# primary_cap_int_-_Copy.net
KiCad netlist of a schematic drawn in Altium Designer
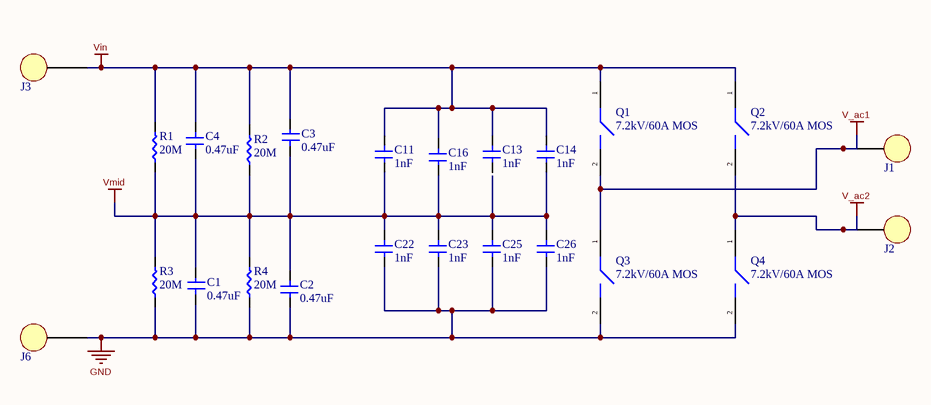
[diagram p0: primary_cap_int - Copy.SchDoc]

(export (version "E")
  (design (tool "Eeschema 10.0.6"))
  (components
    (comp (ref "C1")
      (value "0.47uF")
      (footprint "C4BSYBX3470ZBMJ")
      (description "Cap, 0.47UF, 750VAC, Film, Radial")
      (fields
        (field (name "MANUFACTURER") "KEMET")
        (field (name "MANUFACTURER PART NUMBER") "C4BSYBX3470ZBMJ")
      )
      (libsource (lib "primary_cap") (part "C4BSYBX3470ZBMJ"))
    )
    (comp (ref "C2")
      (value "0.47uF")
      (footprint "C4BSYBX3470ZBMJ")
      (description "Cap, 0.47UF, 750VAC, Film, Radial")
      (fields
        (field (name "MANUFACTURER") "KEMET")
        (field (name "MANUFACTURER PART NUMBER") "C4BSYBX3470ZBMJ")
      )
      (libsource (lib "primary_cap") (part "C4BSYBX3470ZBMJ"))
    )
    (comp (ref "C3")
      (value "0.47uF")
      (footprint "C4BSYBX3470ZBMJ")
      (description "Cap, 0.47UF, 750VAC, Film, Radial")
      (fields
        (field (name "MANUFACTURER") "KEMET")
        (field (name "MANUFACTURER PART NUMBER") "C4BSYBX3470ZBMJ")
      )
      (libsource (lib "primary_cap") (part "C4BSYBX3470ZBMJ"))
    )
    (comp (ref "C4")
      (value "0.47uF")
      (footprint "C4BSYBX3470ZBMJ")
      (description "Cap, 0.47UF, 750VAC, Film, Radial")
      (fields
        (field (name "MANUFACTURER") "KEMET")
        (field (name "MANUFACTURER PART NUMBER") "C4BSYBX3470ZBMJ")
      )
      (libsource (lib "primary_cap") (part "C4BSYBX3470ZBMJ"))
    )
    (comp (ref "C11")
      (value "1nF")
      (footprint "PHE450XB4100JB04R17")
      (description "CAP FILM 1000PF 5% 3KVDC RADIAL")
      (fields
        (field (name "MANUFACTURER") "KEMET")
        (field (name "MANUFACTURER PART NUMBER") "PHE450XB4100JB04R17")
      )
      (libsource (lib "primary_cap") (part "PHE450XB4100JB04R17"))
    )
    (comp (ref "C13")
      (value "1nF")
      (footprint "PHE450XB4100JB04R17")
      (description "CAP FILM 1000PF 5% 3KVDC RADIAL")
      (fields
        (field (name "MANUFACTURER") "KEMET")
        (field (name "MANUFACTURER PART NUMBER") "PHE450XB4100JB04R17")
      )
      (libsource (lib "primary_cap") (part "PHE450XB4100JB04R17"))
    )
    (comp (ref "C14")
      (value "1nF")
      (footprint "PHE450XB4100JB04R17")
      (description "CAP FILM 1000PF 5% 3KVDC RADIAL")
      (fields
        (field (name "MANUFACTURER") "KEMET")
        (field (name "MANUFACTURER PART NUMBER") "PHE450XB4100JB04R17")
      )
      (libsource (lib "primary_cap") (part "PHE450XB4100JB04R17"))
    )
    (comp (ref "C16")
      (value "1nF")
      (footprint "PHE450XB4100JB04R17")
      (description "CAP FILM 1000PF 5% 3KVDC RADIAL")
      (fields
        (field (name "MANUFACTURER") "KEMET")
        (field (name "MANUFACTURER PART NUMBER") "PHE450XB4100JB04R17")
      )
      (libsource (lib "primary_cap") (part "PHE450XB4100JB04R17"))
    )
    (comp (ref "C22")
      (value "1nF")
      (footprint "PHE450XB4100JB04R17")
      (description "CAP FILM 1000PF 5% 3KVDC RADIAL")
      (fields
        (field (name "MANUFACTURER") "KEMET")
        (field (name "MANUFACTURER PART NUMBER") "PHE450XB4100JB04R17")
      )
      (libsource (lib "primary_cap") (part "PHE450XB4100JB04R17"))
    )
    (comp (ref "C23")
      (value "1nF")
      (footprint "PHE450XB4100JB04R17")
      (description "CAP FILM 1000PF 5% 3KVDC RADIAL")
      (fields
        (field (name "MANUFACTURER") "KEMET")
        (field (name "MANUFACTURER PART NUMBER") "PHE450XB4100JB04R17")
      )
      (libsource (lib "primary_cap") (part "PHE450XB4100JB04R17"))
    )
    (comp (ref "C25")
      (value "1nF")
      (footprint "PHE450XB4100JB04R17")
      (description "CAP FILM 1000PF 5% 3KVDC RADIAL")
      (fields
        (field (name "MANUFACTURER") "KEMET")
        (field (name "MANUFACTURER PART NUMBER") "PHE450XB4100JB04R17")
      )
      (libsource (lib "primary_cap") (part "PHE450XB4100JB04R17"))
    )
    (comp (ref "C26")
      (value "1nF")
      (footprint "PHE450XB4100JB04R17")
      (description "CAP FILM 1000PF 5% 3KVDC RADIAL")
      (fields
        (field (name "MANUFACTURER") "KEMET")
        (field (name "MANUFACTURER PART NUMBER") "PHE450XB4100JB04R17")
      )
      (libsource (lib "primary_cap") (part "PHE450XB4100JB04R17"))
    )
    (comp (ref "J1")
      (value "TERM PCB SNAP-IN VERT HD M5 THRD")
      (footprint "M4_9pin_shank")
      (fields
        (field (name "MANUFACTURER") "Keystone Electronics")
        (field (name "MANUFACTURER PART NUMBER") "7807")
      )
      (libsource (lib "diodebridge") (part "7807"))
    )
    (comp (ref "J2")
      (value "TERM PCB SNAP-IN VERT HD M5 THRD")
      (footprint "M4_9pin_shank")
      (fields
        (field (name "MANUFACTURER") "Keystone Electronics")
        (field (name "MANUFACTURER PART NUMBER") "7807")
      )
      (libsource (lib "diodebridge") (part "7807"))
    )
    (comp (ref "J3")
      (value "TERM PCB SNAP-IN VERT HD M5 THRD")
      (footprint "M4_9pin_shank")
      (fields
        (field (name "MANUFACTURER") "Keystone Electronics")
        (field (name "MANUFACTURER PART NUMBER") "7807")
      )
      (libsource (lib "diodebridge") (part "7807"))
    )
    (comp (ref "J6")
      (value "TERM PCB SNAP-IN VERT HD M5 THRD")
      (footprint "M4_9pin_shank")
      (fields
        (field (name "MANUFACTURER") "Keystone Electronics")
        (field (name "MANUFACTURER PART NUMBER") "7807")
      )
      (libsource (lib "diodebridge") (part "7807"))
    )
    (comp (ref "Q1")
      (value "7.2kV/60A MOS")
      (footprint "Austin Supermos_r1")
      (libsource (lib "primary_cap") (part "Austin SuperMos"))
    )
    (comp (ref "Q2")
      (value "7.2kV/60A MOS")
      (footprint "Austin Supermos_r1")
      (libsource (lib "primary_cap") (part "Austin SuperMos"))
    )
    (comp (ref "Q3")
      (value "7.2kV/60A MOS")
      (footprint "Austin Supermos_r1")
      (libsource (lib "primary_cap") (part "Austin SuperMos"))
    )
    (comp (ref "Q4")
      (value "7.2kV/60A MOS")
      (footprint "Austin Supermos_r1")
      (libsource (lib "primary_cap") (part "Austin SuperMos"))
    )
    (comp (ref "R1")
      (value "20M")
      (footprint "VR37000002005JR500")
      (description "RES 20M OHM 1/2W 5% AXIAL")
      (fields
        (field (name "MANUFACTURER") "Vishay BCcomponents")
        (field (name "MANUFACTURER PART NUMBER") "VR37000002005JR500")
      )
      (libsource (lib "primary_cap") (part "VR37000002005JR500"))
    )
    (comp (ref "R2")
      (value "20M")
      (footprint "VR37000002005JR500")
      (description "RES 20M OHM 1/2W 5% AXIAL")
      (fields
        (field (name "MANUFACTURER") "Vishay BCcomponents")
        (field (name "MANUFACTURER PART NUMBER") "VR37000002005JR500")
      )
      (libsource (lib "primary_cap") (part "VR37000002005JR500"))
    )
    (comp (ref "R3")
      (value "20M")
      (footprint "VR37000002005JR500")
      (description "RES 20M OHM 1/2W 5% AXIAL")
      (fields
        (field (name "MANUFACTURER") "Vishay BCcomponents")
        (field (name "MANUFACTURER PART NUMBER") "VR37000002005JR500")
      )
      (libsource (lib "primary_cap") (part "VR37000002005JR500"))
    )
    (comp (ref "R4")
      (value "20M")
      (footprint "VR37000002005JR500")
      (description "RES 20M OHM 1/2W 5% AXIAL")
      (fields
        (field (name "MANUFACTURER") "Vishay BCcomponents")
        (field (name "MANUFACTURER PART NUMBER") "VR37000002005JR500")
      )
      (libsource (lib "primary_cap") (part "VR37000002005JR500"))
    )
  )
  (nets
    (net (code "1") (name "GND") (class "Default")
      (node (ref "C1") (pin "2") (pinfunction "2_2") (pintype "passive"))
      (node (ref "C2") (pin "1") (pinfunction "1_1") (pintype "passive"))
      (node (ref "C22") (pin "1") (pinfunction "1_1") (pintype "passive"))
      (node (ref "C23") (pin "1") (pinfunction "1_1") (pintype "passive"))
      (node (ref "C25") (pin "1") (pinfunction "1_1") (pintype "passive"))
      (node (ref "C26") (pin "1") (pinfunction "1_1") (pintype "passive"))
      (node (ref "J6") (pin "1") (pinfunction "1_1") (pintype "passive"))
      (node (ref "Q3") (pin "2") (pinfunction "2_2") (pintype "power_in"))
      (node (ref "Q4") (pin "2") (pinfunction "2_2") (pintype "power_in"))
      (node (ref "R3") (pin "1") (pinfunction "3_1") (pintype "passive"))
      (node (ref "R4") (pin "1") (pinfunction "3_1") (pintype "passive"))
    )
    (net (code "2") (name "V_ac1") (class "Default")
      (node (ref "J1") (pin "1") (pinfunction "1_1") (pintype "passive"))
      (node (ref "Q1") (pin "2") (pinfunction "2_2") (pintype "power_in"))
      (node (ref "Q3") (pin "1") (pinfunction "1_1") (pintype "power_in"))
    )
    (net (code "3") (name "V_ac2") (class "Default")
      (node (ref "J2") (pin "1") (pinfunction "1_1") (pintype "passive"))
      (node (ref "Q2") (pin "2") (pinfunction "2_2") (pintype "power_in"))
      (node (ref "Q4") (pin "1") (pinfunction "1_1") (pintype "power_in"))
    )
    (net (code "4") (name "Vin") (class "Default")
      (node (ref "C11") (pin "2") (pinfunction "2_2") (pintype "passive"))
      (node (ref "C13") (pin "2") (pinfunction "2_2") (pintype "passive"))
      (node (ref "C14") (pin "2") (pinfunction "2_2") (pintype "passive"))
      (node (ref "C16") (pin "2") (pinfunction "2_2") (pintype "passive"))
      (node (ref "C3") (pin "1") (pinfunction "1_1") (pintype "passive"))
      (node (ref "C4") (pin "2") (pinfunction "2_2") (pintype "passive"))
      (node (ref "J3") (pin "1") (pinfunction "1_1") (pintype "passive"))
      (node (ref "Q1") (pin "1") (pinfunction "1_1") (pintype "power_in"))
      (node (ref "Q2") (pin "1") (pinfunction "1_1") (pintype "power_in"))
      (node (ref "R1") (pin "2") (pinfunction "4_2") (pintype "passive"))
      (node (ref "R2") (pin "2") (pinfunction "4_2") (pintype "passive"))
    )
    (net (code "5") (name "Vmid") (class "Default")
      (node (ref "C1") (pin "1") (pinfunction "1_1") (pintype "passive"))
      (node (ref "C11") (pin "1") (pinfunction "1_1") (pintype "passive"))
      (node (ref "C14") (pin "1") (pinfunction "1_1") (pintype "passive"))
      (node (ref "C16") (pin "1") (pinfunction "1_1") (pintype "passive"))
      (node (ref "C2") (pin "2") (pinfunction "2_2") (pintype "passive"))
      (node (ref "C22") (pin "2") (pinfunction "2_2") (pintype "passive"))
      (node (ref "C23") (pin "2") (pinfunction "2_2") (pintype "passive"))
      (node (ref "C25") (pin "2") (pinfunction "2_2") (pintype "passive"))
      (node (ref "C26") (pin "2") (pinfunction "2_2") (pintype "passive"))
      (node (ref "C3") (pin "2") (pinfunction "2_2") (pintype "passive"))
      (node (ref "C4") (pin "1") (pinfunction "1_1") (pintype "passive"))
      (node (ref "R1") (pin "1") (pinfunction "3_1") (pintype "passive"))
      (node (ref "R2") (pin "1") (pinfunction "3_1") (pintype "passive"))
      (node (ref "R3") (pin "2") (pinfunction "4_2") (pintype "passive"))
      (node (ref "R4") (pin "2") (pinfunction "4_2") (pintype "passive"))
    )
    (net (code "6") (name "unconnected-(C13-Pad1)") (class "Default")
      (node (ref "C13") (pin "1") (pinfunction "1_1") (pintype "passive"))
    )
  )
)
